# 8_RK3399_SDIO_SPI_GPIOs.net
KiCad netlist of a schematic drawn in Altium Designer
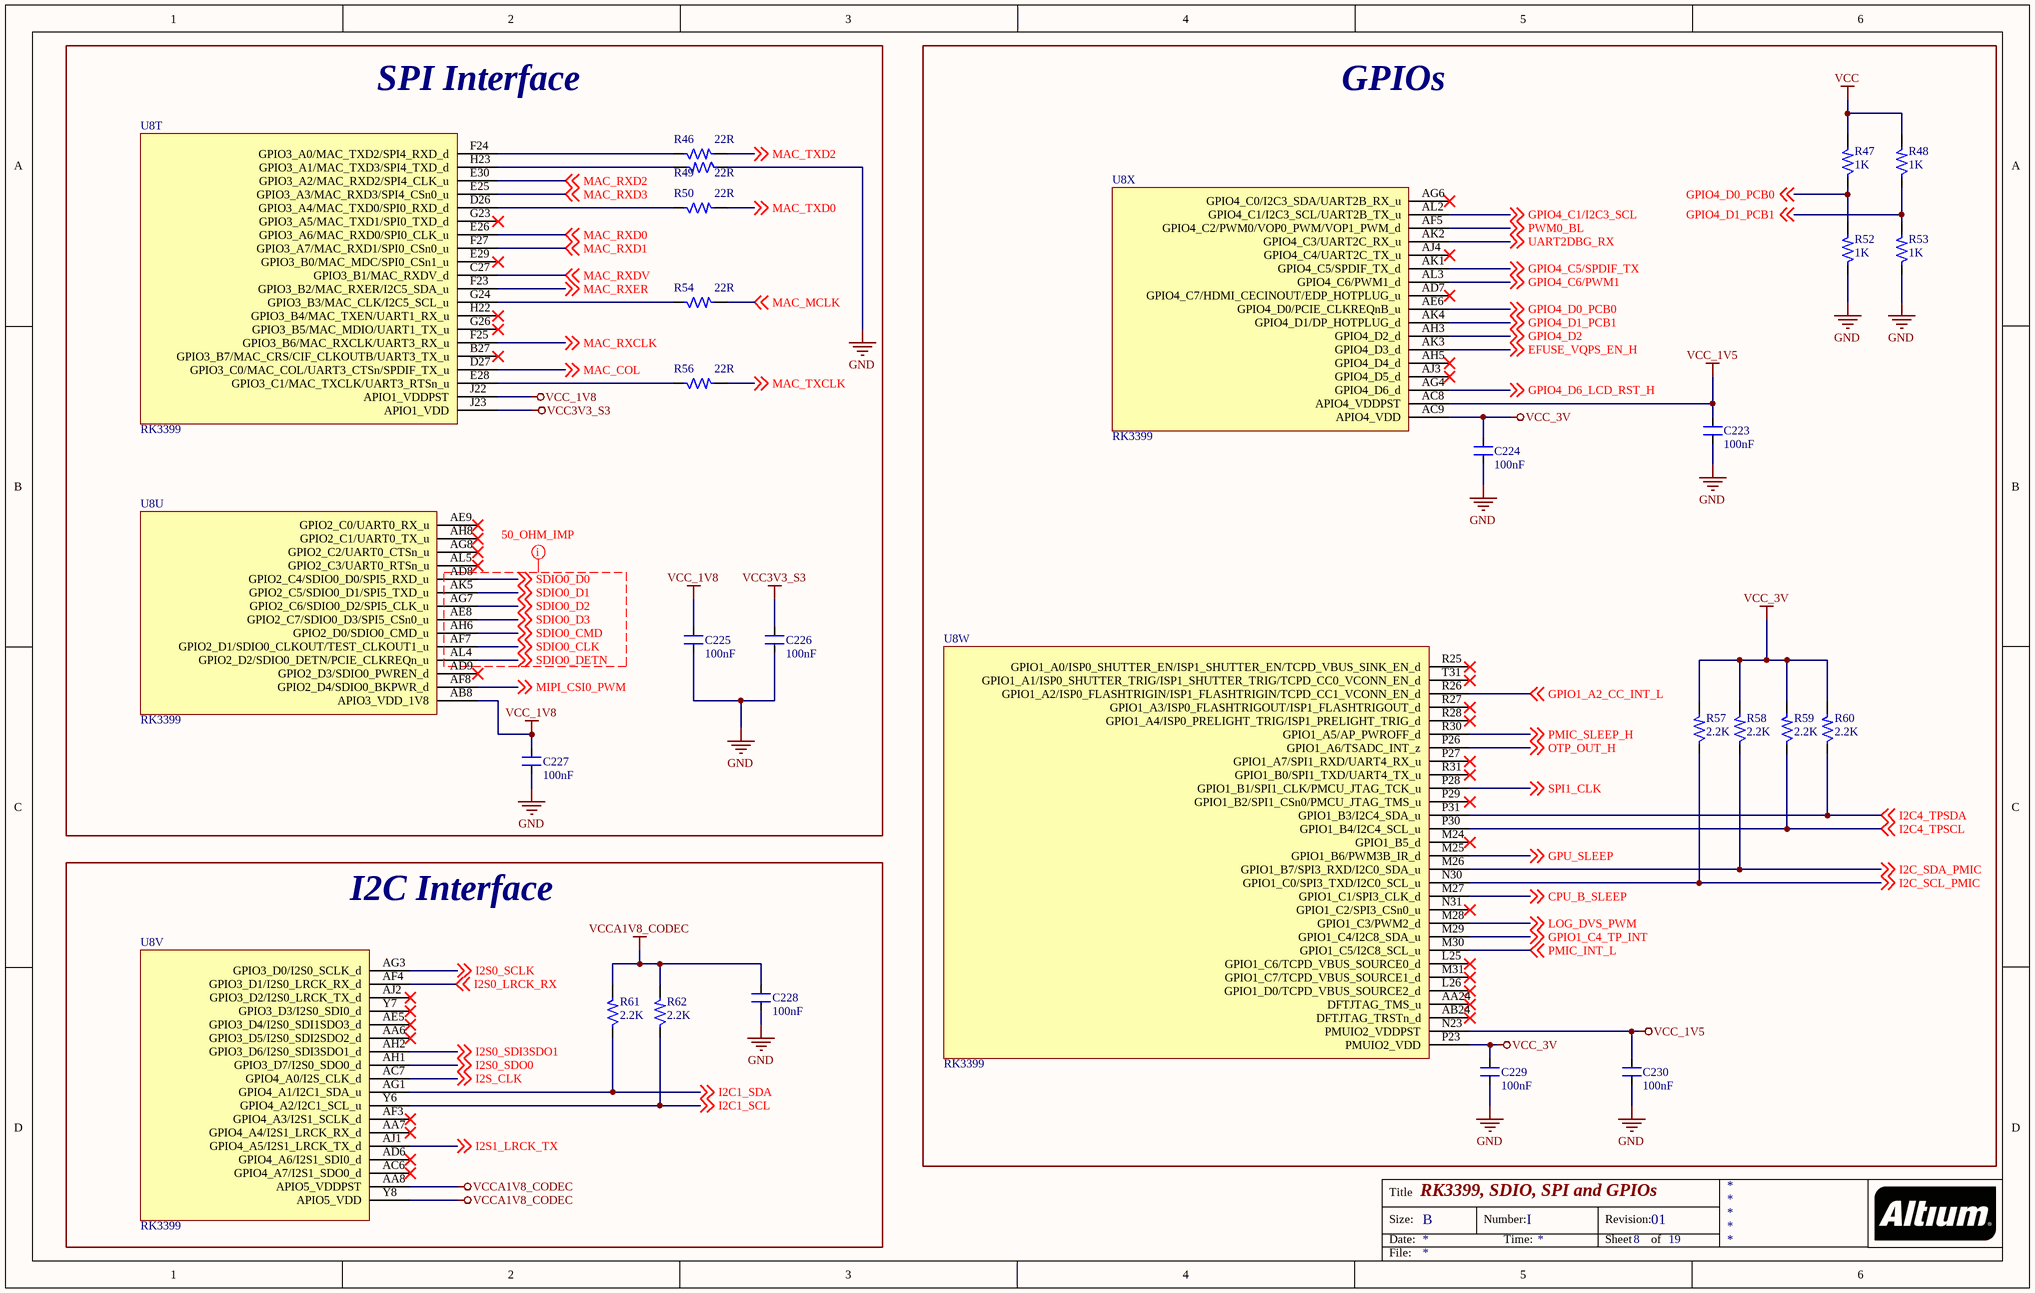
[diagram p0: [8] RK3399_SDIO_SPI_GPIOs.SchDoc]

(export (version "E")
  (design (tool "Eeschema 10.0.6"))
  (components
    (comp (ref "C223")
      (value "100nF")
      (footprint "CAP_0201")
      (description "0.1µF ±10% 25V Ceramic Capacitor X5R 0201 (0603 Metric)")
      (fields
        (field (name "MANUFACTURER") "TDK Corporation")
        (field (name "MANUFACTURER PART NUMBER") "C0603X5R1E104K030BB")
      )
      (libsource (lib "EsteemPCB_SOM_Course_intlib") (part "CAP_100nF-25V-10%-0201"))
    )
    (comp (ref "C224")
      (value "100nF")
      (footprint "CAP_0201")
      (description "0.1µF ±10% 25V Ceramic Capacitor X5R 0201 (0603 Metric)")
      (fields
        (field (name "MANUFACTURER") "TDK Corporation")
        (field (name "MANUFACTURER PART NUMBER") "C0603X5R1E104K030BB")
      )
      (libsource (lib "EsteemPCB_SOM_Course_intlib") (part "CAP_100nF-25V-10%-0201"))
    )
    (comp (ref "C225")
      (value "100nF")
      (footprint "CAP_0201")
      (description "0.1µF ±10% 25V Ceramic Capacitor X5R 0201 (0603 Metric)")
      (fields
        (field (name "MANUFACTURER") "TDK Corporation")
        (field (name "MANUFACTURER PART NUMBER") "C0603X5R1E104K030BB")
      )
      (libsource (lib "EsteemPCB_SOM_Course_intlib") (part "CAP_100nF-25V-10%-0201"))
    )
    (comp (ref "C226")
      (value "100nF")
      (footprint "CAP_0201")
      (description "0.1µF ±10% 25V Ceramic Capacitor X5R 0201 (0603 Metric)")
      (fields
        (field (name "MANUFACTURER") "TDK Corporation")
        (field (name "MANUFACTURER PART NUMBER") "C0603X5R1E104K030BB")
      )
      (libsource (lib "EsteemPCB_SOM_Course_intlib") (part "CAP_100nF-25V-10%-0201"))
    )
    (comp (ref "C227")
      (value "100nF")
      (footprint "CAP_0201")
      (description "0.1µF ±10% 25V Ceramic Capacitor X5R 0201 (0603 Metric)")
      (fields
        (field (name "MANUFACTURER") "TDK Corporation")
        (field (name "MANUFACTURER PART NUMBER") "C0603X5R1E104K030BB")
      )
      (libsource (lib "EsteemPCB_SOM_Course_intlib") (part "CAP_100nF-25V-10%-0201"))
    )
    (comp (ref "C228")
      (value "100nF")
      (footprint "CAP_0201")
      (description "0.1µF ±10% 25V Ceramic Capacitor X5R 0201 (0603 Metric)")
      (fields
        (field (name "MANUFACTURER") "TDK Corporation")
        (field (name "MANUFACTURER PART NUMBER") "C0603X5R1E104K030BB")
      )
      (libsource (lib "EsteemPCB_SOM_Course_intlib") (part "CAP_100nF-25V-10%-0201"))
    )
    (comp (ref "C229")
      (value "100nF")
      (footprint "CAP_0201")
      (description "0.1µF ±10% 25V Ceramic Capacitor X5R 0201 (0603 Metric)")
      (fields
        (field (name "MANUFACTURER") "TDK Corporation")
        (field (name "MANUFACTURER PART NUMBER") "C0603X5R1E104K030BB")
      )
      (libsource (lib "EsteemPCB_SOM_Course_intlib") (part "CAP_100nF-25V-10%-0201"))
    )
    (comp (ref "C230")
      (value "100nF")
      (footprint "CAP_0201")
      (description "0.1µF ±10% 25V Ceramic Capacitor X5R 0201 (0603 Metric)")
      (fields
        (field (name "MANUFACTURER") "TDK Corporation")
        (field (name "MANUFACTURER PART NUMBER") "C0603X5R1E104K030BB")
      )
      (libsource (lib "EsteemPCB_SOM_Course_intlib") (part "CAP_100nF-25V-10%-0201"))
    )
    (comp (ref "R46")
      (value "22R")
      (footprint "RES_0201")
      (description "22 Ohms ±1% 0.05W, 1/20W Chip Resistor 0201 (0603 Metric) Moisture Resistant Thick Film")
      (fields
        (field (name "MANUFACTURER") "Yageo")
        (field (name "MANUFACTURER PART NUMBER") "RC0201FR-0722RL")
      )
      (libsource (lib "EsteemPCB_SOM_Course_intlib") (part "RES_22R-0.05W-1%-0201"))
    )
    (comp (ref "R47")
      (value "1K")
      (footprint "RES_0201")
      (description "1 kOhms ±1% 0.05W, 1/20W Chip Resistor 0201 (0603 Metric) Thick Film")
      (fields
        (field (name "MANUFACTURER") "Yageo")
        (field (name "MANUFACTURER PART NUMBER") "RC0201FR-071KL")
      )
      (libsource (lib "EsteemPCB_SOM_Course_intlib") (part "RES_1K-0.05W-1%-0201"))
    )
    (comp (ref "R48")
      (value "1K")
      (footprint "RES_0201")
      (description "1 kOhms ±1% 0.05W, 1/20W Chip Resistor 0201 (0603 Metric) Thick Film")
      (fields
        (field (name "MANUFACTURER") "Yageo")
        (field (name "MANUFACTURER PART NUMBER") "RC0201FR-071KL")
      )
      (libsource (lib "EsteemPCB_SOM_Course_intlib") (part "RES_1K-0.05W-1%-0201"))
    )
    (comp (ref "R49")
      (value "22R")
      (footprint "RES_0201")
      (description "22 Ohms ±1% 0.05W, 1/20W Chip Resistor 0201 (0603 Metric) Moisture Resistant Thick Film")
      (fields
        (field (name "MANUFACTURER") "Yageo")
        (field (name "MANUFACTURER PART NUMBER") "RC0201FR-0722RL")
      )
      (libsource (lib "EsteemPCB_SOM_Course_intlib") (part "RES_22R-0.05W-1%-0201"))
    )
    (comp (ref "R50")
      (value "22R")
      (footprint "RES_0201")
      (description "22 Ohms ±1% 0.05W, 1/20W Chip Resistor 0201 (0603 Metric) Moisture Resistant Thick Film")
      (fields
        (field (name "MANUFACTURER") "Yageo")
        (field (name "MANUFACTURER PART NUMBER") "RC0201FR-0722RL")
      )
      (libsource (lib "EsteemPCB_SOM_Course_intlib") (part "RES_22R-0.05W-1%-0201"))
    )
    (comp (ref "R52")
      (value "1K")
      (footprint "RES_0402")
      (description "1 kOhms ±1% 0.1W, 1/10W Chip Resistor 0402 (1005 Metric) Anti-Sulfur Thin Film")
      (fields
        (field (name "MANUFACTURER") "Vishay Beyschlag/Draloric/BC Components")
        (field (name "MANUFACTURER PART NUMBER") "MCS04020C1001FE000")
      )
      (libsource (lib "EsteemPCB_SOM_Course_intlib") (part "RES_1K-0.1W-1%-0402"))
    )
    (comp (ref "R53")
      (value "1K")
      (footprint "RES_0402")
      (description "1 kOhms ±1% 0.1W, 1/10W Chip Resistor 0402 (1005 Metric) Anti-Sulfur Thin Film")
      (fields
        (field (name "MANUFACTURER") "Vishay Beyschlag/Draloric/BC Components")
        (field (name "MANUFACTURER PART NUMBER") "MCS04020C1001FE000")
      )
      (libsource (lib "EsteemPCB_SOM_Course_intlib") (part "RES_1K-0.1W-1%-0402"))
    )
    (comp (ref "R54")
      (value "22R")
      (footprint "RES_0201")
      (description "22 Ohms ±1% 0.05W, 1/20W Chip Resistor 0201 (0603 Metric) Moisture Resistant Thick Film")
      (fields
        (field (name "MANUFACTURER") "Yageo")
        (field (name "MANUFACTURER PART NUMBER") "RC0201FR-0722RL")
      )
      (libsource (lib "EsteemPCB_SOM_Course_intlib") (part "RES_22R-0.05W-1%-0201"))
    )
    (comp (ref "R56")
      (value "22R")
      (footprint "RES_0201")
      (description "22 Ohms ±1% 0.05W, 1/20W Chip Resistor 0201 (0603 Metric) Moisture Resistant Thick Film")
      (fields
        (field (name "MANUFACTURER") "Yageo")
        (field (name "MANUFACTURER PART NUMBER") "RC0201FR-0722RL")
      )
      (libsource (lib "EsteemPCB_SOM_Course_intlib") (part "RES_22R-0.05W-1%-0201"))
    )
    (comp (ref "R57")
      (value "2.2K")
      (footprint "RES_0201")
      (description "2.2 kOhms ±1% 0.05W, 1/20W Chip Resistor 0201 (0603 Metric) Thick Film")
      (fields
        (field (name "MANUFACTURER") "Stackpole Electronics Inc")
        (field (name "MANUFACTURER PART NUMBER") "RMCF0201FT2K20")
      )
      (libsource (lib "EsteemPCB_SOM_Course_intlib") (part "RES_2.2K-0.05W-1%-0201"))
    )
    (comp (ref "R58")
      (value "2.2K")
      (footprint "RES_0201")
      (description "2.2 kOhms ±1% 0.05W, 1/20W Chip Resistor 0201 (0603 Metric) Thick Film")
      (fields
        (field (name "MANUFACTURER") "Stackpole Electronics Inc")
        (field (name "MANUFACTURER PART NUMBER") "RMCF0201FT2K20")
      )
      (libsource (lib "EsteemPCB_SOM_Course_intlib") (part "RES_2.2K-0.05W-1%-0201"))
    )
    (comp (ref "R59")
      (value "2.2K")
      (footprint "RES_0201")
      (description "2.2 kOhms ±1% 0.05W, 1/20W Chip Resistor 0201 (0603 Metric) Thick Film")
      (fields
        (field (name "MANUFACTURER") "Stackpole Electronics Inc")
        (field (name "MANUFACTURER PART NUMBER") "RMCF0201FT2K20")
      )
      (libsource (lib "EsteemPCB_SOM_Course_intlib") (part "RES_2.2K-0.05W-1%-0201"))
    )
    (comp (ref "R60")
      (value "2.2K")
      (footprint "RES_0201")
      (description "2.2 kOhms ±1% 0.05W, 1/20W Chip Resistor 0201 (0603 Metric) Thick Film")
      (fields
        (field (name "MANUFACTURER") "Stackpole Electronics Inc")
        (field (name "MANUFACTURER PART NUMBER") "RMCF0201FT2K20")
      )
      (libsource (lib "EsteemPCB_SOM_Course_intlib") (part "RES_2.2K-0.05W-1%-0201"))
    )
    (comp (ref "R61")
      (value "2.2K")
      (footprint "RES_0201")
      (description "2.2 kOhms ±1% 0.05W, 1/20W Chip Resistor 0201 (0603 Metric) Thick Film")
      (fields
        (field (name "MANUFACTURER") "Stackpole Electronics Inc")
        (field (name "MANUFACTURER PART NUMBER") "RMCF0201FT2K20")
      )
      (libsource (lib "EsteemPCB_SOM_Course_intlib") (part "RES_2.2K-0.05W-1%-0201"))
    )
    (comp (ref "R62")
      (value "2.2K")
      (footprint "RES_0201")
      (description "2.2 kOhms ±1% 0.05W, 1/20W Chip Resistor 0201 (0603 Metric) Thick Film")
      (fields
        (field (name "MANUFACTURER") "Stackpole Electronics Inc")
        (field (name "MANUFACTURER PART NUMBER") "RMCF0201FT2K20")
      )
      (libsource (lib "EsteemPCB_SOM_Course_intlib") (part "RES_2.2K-0.05W-1%-0201"))
    )
    (comp (ref "U8")
      (value "RK3399")
      (footprint "FBGA828_23_826X826")
      (description "RK3399 is a low power, high performance processor for computing, personal mobile.")
      (fields (field (name "MANUFACTURER") "Rockchip"))
      (libsource (lib "EsteemPCB_SOM_Course_intlib") (part "IC_RK3399-FCBGA828"))
    )
  )
  (nets
    (net (code "1") (name "CPU_B_SLEEP") (class "Default")
      (node (ref "U8") (pin "M27") (pinfunction "GPIO1_C1/SPI3_CLK_d_M27") (pintype "passive"))
    )
    (net (code "2") (name "EFUSE_VQPS_EN_H") (class "Default")
      (node (ref "U8") (pin "AK3") (pinfunction "GPIO4_D3_d_AK3") (pintype "passive"))
    )
    (net (code "3") (name "GND") (class "Default")
      (node (ref "C223") (pin "1") (pinfunction "1_1") (pintype "passive"))
      (node (ref "C224") (pin "1") (pinfunction "1_1") (pintype "passive"))
      (node (ref "C225") (pin "1") (pinfunction "1_1") (pintype "passive"))
      (node (ref "C226") (pin "1") (pinfunction "1_1") (pintype "passive"))
      (node (ref "C227") (pin "1") (pinfunction "1_1") (pintype "passive"))
      (node (ref "C228") (pin "1") (pinfunction "1_1") (pintype "passive"))
      (node (ref "C229") (pin "1") (pinfunction "1_1") (pintype "passive"))
      (node (ref "C230") (pin "1") (pinfunction "1_1") (pintype "passive"))
      (node (ref "R49") (pin "1") (pinfunction "1_1") (pintype "passive"))
      (node (ref "R52") (pin "1") (pinfunction "1_1") (pintype "passive"))
      (node (ref "R53") (pin "1") (pinfunction "1_1") (pintype "passive"))
    )
    (net (code "4") (name "GPIO1_A2_CC_INT_L") (class "Default")
      (node (ref "U8") (pin "R26") (pinfunction "GPIO1_A2/ISP0_FLASHTRIGIN/ISP1_FLASHTRIGIN/TCPD_CC1_VCONN_EN_d_R26") (pintype "passive"))
    )
    (net (code "5") (name "GPIO1_C4_TP_INT") (class "Default")
      (node (ref "U8") (pin "M29") (pinfunction "GPIO1_C4/I2C8_SDA_u_M29") (pintype "passive"))
    )
    (net (code "6") (name "GPIO4_C1{slash}I2C3_SCL") (class "Default")
      (node (ref "U8") (pin "AL2") (pinfunction "GPIO4_C1/I2C3_SCL/UART2B_TX_u_AL2") (pintype "passive"))
    )
    (net (code "7") (name "GPIO4_C5{slash}SPDIF_TX") (class "Default")
      (node (ref "U8") (pin "AK1") (pinfunction "GPIO4_C5/SPDIF_TX_d_AK1") (pintype "passive"))
    )
    (net (code "8") (name "GPIO4_C6{slash}PWM1") (class "Default")
      (node (ref "U8") (pin "AL3") (pinfunction "GPIO4_C6/PWM1_d_AL3") (pintype "passive"))
    )
    (net (code "9") (name "GPIO4_D0_PCB0") (class "Default")
      (node (ref "R47") (pin "1") (pinfunction "1_1") (pintype "passive"))
      (node (ref "R52") (pin "2") (pinfunction "2_2") (pintype "passive"))
      (node (ref "U8") (pin "AE6") (pinfunction "GPIO4_D0/PCIE_CLKREQnB_u_AE6") (pintype "passive"))
    )
    (net (code "10") (name "GPIO4_D1_PCB1") (class "Default")
      (node (ref "R48") (pin "1") (pinfunction "1_1") (pintype "passive"))
      (node (ref "R53") (pin "2") (pinfunction "2_2") (pintype "passive"))
      (node (ref "U8") (pin "AK4") (pinfunction "GPIO4_D1/DP_HOTPLUG_d_AK4") (pintype "passive"))
    )
    (net (code "11") (name "GPIO4_D2") (class "Default")
      (node (ref "U8") (pin "AH3") (pinfunction "GPIO4_D2_d_AH3") (pintype "passive"))
    )
    (net (code "12") (name "GPIO4_D6_LCD_RST_H") (class "Default")
      (node (ref "U8") (pin "AG4") (pinfunction "GPIO4_D6_d_AG4") (pintype "passive"))
    )
    (net (code "13") (name "GPU_SLEEP") (class "Default")
      (node (ref "U8") (pin "M25") (pinfunction "GPIO1_B6/PWM3B_IR_d_M25") (pintype "passive"))
    )
    (net (code "14") (name "I2C1_SCL") (class "Default")
      (node (ref "R62") (pin "1") (pinfunction "1_1") (pintype "passive"))
      (node (ref "U8") (pin "Y6") (pinfunction "GPIO4_A2/I2C1_SCL_u_Y6") (pintype "passive"))
    )
    (net (code "15") (name "I2C1_SDA") (class "Default")
      (node (ref "R61") (pin "1") (pinfunction "1_1") (pintype "passive"))
      (node (ref "U8") (pin "AG1") (pinfunction "GPIO4_A1/I2C1_SDA_u_AG1") (pintype "passive"))
    )
    (net (code "16") (name "I2C4_TPSCL") (class "Default")
      (node (ref "R59") (pin "1") (pinfunction "1_1") (pintype "passive"))
      (node (ref "U8") (pin "P30") (pinfunction "GPIO1_B4/I2C4_SCL_u_P30") (pintype "passive"))
    )
    (net (code "17") (name "I2C4_TPSDA") (class "Default")
      (node (ref "R60") (pin "1") (pinfunction "1_1") (pintype "passive"))
      (node (ref "U8") (pin "P31") (pinfunction "GPIO1_B3/I2C4_SDA_u_P31") (pintype "passive"))
    )
    (net (code "18") (name "I2C_SCL_PMIC") (class "Default")
      (node (ref "R57") (pin "1") (pinfunction "1_1") (pintype "passive"))
      (node (ref "U8") (pin "N30") (pinfunction "GPIO1_C0/SPI3_TXD/I2C0_SCL_u_N30") (pintype "passive"))
    )
    (net (code "19") (name "I2C_SDA_PMIC") (class "Default")
      (node (ref "R58") (pin "1") (pinfunction "1_1") (pintype "passive"))
      (node (ref "U8") (pin "M26") (pinfunction "GPIO1_B7/SPI3_RXD/I2C0_SDA_u_M26") (pintype "passive"))
    )
    (net (code "20") (name "I2S0_LRCK_RX") (class "Default")
      (node (ref "U8") (pin "AF4") (pinfunction "GPIO3_D1/I2S0_LRCK_RX_d_AF4") (pintype "passive"))
    )
    (net (code "21") (name "I2S0_SCLK") (class "Default")
      (node (ref "U8") (pin "AG3") (pinfunction "GPIO3_D0/I2S0_SCLK_d_AG3") (pintype "passive"))
    )
    (net (code "22") (name "I2S0_SDI3SDO1") (class "Default")
      (node (ref "U8") (pin "AH2") (pinfunction "GPIO3_D6/I2S0_SDI3SDO1_d_AH2") (pintype "passive"))
    )
    (net (code "23") (name "I2S0_SDO0") (class "Default")
      (node (ref "U8") (pin "AH1") (pinfunction "GPIO3_D7/I2S0_SDO0_d_AH1") (pintype "passive"))
    )
    (net (code "24") (name "I2S1_LRCK_TX") (class "Default")
      (node (ref "U8") (pin "AJ1") (pinfunction "GPIO4_A5/I2S1_LRCK_TX_d_AJ1") (pintype "passive"))
    )
    (net (code "25") (name "I2S_CLK") (class "Default")
      (node (ref "U8") (pin "AC7") (pinfunction "GPIO4_A0/I2S_CLK_d_AC7") (pintype "passive"))
    )
    (net (code "26") (name "LOG_DVS_PWM") (class "Default")
      (node (ref "U8") (pin "M28") (pinfunction "GPIO1_C3/PWM2_d_M28") (pintype "passive"))
    )
    (net (code "27") (name "MAC_COL") (class "Default")
      (node (ref "U8") (pin "D27") (pinfunction "GPIO3_C0/MAC_COL/UART3_CTSn/SPDIF_TX_u_D27") (pintype "passive"))
    )
    (net (code "28") (name "MAC_MCLK") (class "Default")
      (node (ref "R54") (pin "2") (pinfunction "2_2") (pintype "passive"))
    )
    (net (code "29") (name "MAC_RXCLK") (class "Default")
      (node (ref "U8") (pin "F25") (pinfunction "GPIO3_B6/MAC_RXCLK/UART3_RX_u_F25") (pintype "passive"))
    )
    (net (code "30") (name "MAC_RXD0") (class "Default")
      (node (ref "U8") (pin "E26") (pinfunction "GPIO3_A6/MAC_RXD0/SPI0_CLK_u_E26") (pintype "passive"))
    )
    (net (code "31") (name "MAC_RXD1") (class "Default")
      (node (ref "U8") (pin "F27") (pinfunction "GPIO3_A7/MAC_RXD1/SPI0_CSn0_u_F27") (pintype "passive"))
    )
    (net (code "32") (name "MAC_RXD2") (class "Default")
      (node (ref "U8") (pin "E30") (pinfunction "GPIO3_A2/MAC_RXD2/SPI4_CLK_u_E30") (pintype "passive"))
    )
    (net (code "33") (name "MAC_RXD3") (class "Default")
      (node (ref "U8") (pin "E25") (pinfunction "GPIO3_A3/MAC_RXD3/SPI4_CSn0_u_E25") (pintype "passive"))
    )
    (net (code "34") (name "MAC_RXDV") (class "Default")
      (node (ref "U8") (pin "C27") (pinfunction "GPIO3_B1/MAC_RXDV_d_C27") (pintype "passive"))
    )
    (net (code "35") (name "MAC_RXER") (class "Default")
      (node (ref "U8") (pin "F23") (pinfunction "GPIO3_B2/MAC_RXER/I2C5_SDA_u_F23") (pintype "passive"))
    )
    (net (code "36") (name "MAC_TXCLK") (class "Default")
      (node (ref "R56") (pin "2") (pinfunction "2_2") (pintype "passive"))
    )
    (net (code "37") (name "MAC_TXD0") (class "Default")
      (node (ref "R50") (pin "2") (pinfunction "2_2") (pintype "passive"))
    )
    (net (code "38") (name "MAC_TXD2") (class "Default")
      (node (ref "R46") (pin "2") (pinfunction "2_2") (pintype "passive"))
    )
    (net (code "39") (name "MIPI_CSI0_PWM") (class "Default")
      (node (ref "U8") (pin "AF8") (pinfunction "GPIO2_D4/SDIO0_BKPWR_d_AF8") (pintype "passive"))
    )
    (net (code "40") (name "Net-(U8T-GPIO3_A0{slash}MAC_TXD2{slash}SPI4_RXD_d)") (class "Default")
      (node (ref "R46") (pin "1") (pinfunction "1_1") (pintype "passive"))
      (node (ref "U8") (pin "F24") (pinfunction "GPIO3_A0/MAC_TXD2/SPI4_RXD_d_F24") (pintype "passive"))
    )
    (net (code "41") (name "Net-(U8T-GPIO3_A1{slash}MAC_TXD3{slash}SPI4_TXD_d)") (class "Default")
      (node (ref "R49") (pin "2") (pinfunction "2_2") (pintype "passive"))
      (node (ref "U8") (pin "H23") (pinfunction "GPIO3_A1/MAC_TXD3/SPI4_TXD_d_H23") (pintype "passive"))
    )
    (net (code "42") (name "Net-(U8T-GPIO3_A4{slash}MAC_TXD0{slash}SPI0_RXD_d)") (class "Default")
      (node (ref "R50") (pin "1") (pinfunction "1_1") (pintype "passive"))
      (node (ref "U8") (pin "D26") (pinfunction "GPIO3_A4/MAC_TXD0/SPI0_RXD_d_D26") (pintype "passive"))
    )
    (net (code "43") (name "Net-(U8T-GPIO3_B3{slash}MAC_CLK{slash}I2C5_SCL_u)") (class "Default")
      (node (ref "R54") (pin "1") (pinfunction "1_1") (pintype "passive"))
      (node (ref "U8") (pin "G24") (pinfunction "GPIO3_B3/MAC_CLK/I2C5_SCL_u_G24") (pintype "passive"))
    )
    (net (code "44") (name "Net-(U8T-GPIO3_C1{slash}MAC_TXCLK{slash}UART3_RTSn_u)") (class "Default")
      (node (ref "R56") (pin "1") (pinfunction "1_1") (pintype "passive"))
      (node (ref "U8") (pin "E28") (pinfunction "GPIO3_C1/MAC_TXCLK/UART3_RTSn_u_E28") (pintype "passive"))
    )
    (net (code "45") (name "OTP_OUT_H") (class "Default")
      (node (ref "U8") (pin "P26") (pinfunction "GPIO1_A6/TSADC_INT_z_P26") (pintype "passive"))
    )
    (net (code "46") (name "PMIC_INT_L") (class "Default")
      (node (ref "U8") (pin "M30") (pinfunction "GPIO1_C5/I2C8_SCL_u_M30") (pintype "passive"))
    )
    (net (code "47") (name "PMIC_SLEEP_H") (class "Default")
      (node (ref "U8") (pin "R30") (pinfunction "GPIO1_A5/AP_PWROFF_d_R30") (pintype "passive"))
    )
    (net (code "48") (name "PWM0_BL") (class "Default")
      (node (ref "U8") (pin "AF5") (pinfunction "GPIO4_C2/PWM0/VOP0_PWM/VOP1_PWM_d_AF5") (pintype "passive"))
    )
    (net (code "49") (name "SDIO0_CLK") (class "Default")
      (node (ref "U8") (pin "AF7") (pinfunction "GPIO2_D1/SDIO0_CLKOUT/TEST_CLKOUT1_u_AF7") (pintype "passive"))
    )
    (net (code "50") (name "SDIO0_CMD") (class "Default")
      (node (ref "U8") (pin "AH6") (pinfunction "GPIO2_D0/SDIO0_CMD_u_AH6") (pintype "passive"))
    )
    (net (code "51") (name "SDIO0_D0") (class "Default")
      (node (ref "U8") (pin "AD8") (pinfunction "GPIO2_C4/SDIO0_D0/SPI5_RXD_u_AD8") (pintype "passive"))
    )
    (net (code "52") (name "SDIO0_D1") (class "Default")
      (node (ref "U8") (pin "AK5") (pinfunction "GPIO2_C5/SDIO0_D1/SPI5_TXD_u_AK5") (pintype "passive"))
    )
    (net (code "53") (name "SDIO0_D2") (class "Default")
      (node (ref "U8") (pin "AG7") (pinfunction "GPIO2_C6/SDIO0_D2/SPI5_CLK_u_AG7") (pintype "passive"))
    )
    (net (code "54") (name "SDIO0_D3") (class "Default")
      (node (ref "U8") (pin "AE8") (pinfunction "GPIO2_C7/SDIO0_D3/SPI5_CSn0_u_AE8") (pintype "passive"))
    )
    (net (code "55") (name "SDIO0_DETN") (class "Default")
      (node (ref "U8") (pin "AL4") (pinfunction "GPIO2_D2/SDIO0_DETN/PCIE_CLKREQn_u_AL4") (pintype "passive"))
    )
    (net (code "56") (name "SPI1_CLK") (class "Default")
      (node (ref "U8") (pin "P28") (pinfunction "GPIO1_B1/SPI1_CLK/PMCU_JTAG_TCK_u_P28") (pintype "passive"))
    )
    (net (code "57") (name "UART2DBG_RX") (class "Default")
      (node (ref "U8") (pin "AK2") (pinfunction "GPIO4_C3/UART2C_RX_u_AK2") (pintype "passive"))
    )
    (net (code "58") (name "VCC") (class "Default")
      (node (ref "R47") (pin "2") (pinfunction "2_2") (pintype "passive"))
      (node (ref "R48") (pin "2") (pinfunction "2_2") (pintype "passive"))
    )
    (net (code "59") (name "VCC3V3_S3") (class "Default")
      (node (ref "C226") (pin "2") (pinfunction "2_2") (pintype "passive"))
      (node (ref "U8") (pin "J23") (pinfunction "APIO1_VDD_J23") (pintype "passive"))
    )
    (net (code "60") (name "VCCA1V8_CODEC") (class "Default")
      (node (ref "C228") (pin "2") (pinfunction "2_2") (pintype "passive"))
      (node (ref "R61") (pin "2") (pinfunction "2_2") (pintype "passive"))
      (node (ref "R62") (pin "2") (pinfunction "2_2") (pintype "passive"))
      (node (ref "U8") (pin "AA8") (pinfunction "APIO5_VDDPST_AA8") (pintype "passive"))
      (node (ref "U8") (pin "Y8") (pinfunction "APIO5_VDD_Y8") (pintype "passive"))
    )
    (net (code "61") (name "VCC_1V5") (class "Default")
      (node (ref "C223") (pin "2") (pinfunction "2_2") (pintype "passive"))
      (node (ref "C230") (pin "2") (pinfunction "2_2") (pintype "passive"))
      (node (ref "U8") (pin "AC8") (pinfunction "APIO4_VDDPST_AC8") (pintype "passive"))
      (node (ref "U8") (pin "N23") (pinfunction "PMUIO2_VDDPST_N23") (pintype "passive"))
    )
    (net (code "62") (name "VCC_1V8") (class "Default")
      (node (ref "C225") (pin "2") (pinfunction "2_2") (pintype "passive"))
      (node (ref "C227") (pin "2") (pinfunction "2_2") (pintype "passive"))
      (node (ref "U8") (pin "AB8") (pinfunction "APIO3_VDD_1V8_AB8") (pintype "passive"))
      (node (ref "U8") (pin "J22") (pinfunction "APIO1_VDDPST_J22") (pintype "passive"))
    )
    (net (code "63") (name "VCC_3V") (class "Default")
      (node (ref "C224") (pin "2") (pinfunction "2_2") (pintype "passive"))
      (node (ref "C229") (pin "2") (pinfunction "2_2") (pintype "passive"))
      (node (ref "R57") (pin "2") (pinfunction "2_2") (pintype "passive"))
      (node (ref "R58") (pin "2") (pinfunction "2_2") (pintype "passive"))
      (node (ref "R59") (pin "2") (pinfunction "2_2") (pintype "passive"))
      (node (ref "R60") (pin "2") (pinfunction "2_2") (pintype "passive"))
      (node (ref "U8") (pin "AC9") (pinfunction "APIO4_VDD_AC9") (pintype "passive"))
      (node (ref "U8") (pin "P23") (pinfunction "PMUIO2_VDD_P23") (pintype "passive"))
    )
    (net (code "64") (name "unconnected-(U8T-GPIO3_A5{slash}MAC_TXD1{slash}SPI0_TXD_d-PadG23)") (class "Default")
      (node (ref "U8") (pin "G23") (pinfunction "GPIO3_A5/MAC_TXD1/SPI0_TXD_d_G23") (pintype "passive+no_connect"))
    )
    (net (code "65") (name "unconnected-(U8T-GPIO3_B0{slash}MAC_MDC{slash}SPI0_CSn1_u-PadE29)") (class "Default")
      (node (ref "U8") (pin "E29") (pinfunction "GPIO3_B0/MAC_MDC/SPI0_CSn1_u_E29") (pintype "passive+no_connect"))
    )
    (net (code "66") (name "unconnected-(U8T-GPIO3_B4{slash}MAC_TXEN{slash}UART1_RX_u-PadH22)") (class "Default")
      (node (ref "U8") (pin "H22") (pinfunction "GPIO3_B4/MAC_TXEN/UART1_RX_u_H22") (pintype "passive+no_connect"))
    )
    (net (code "67") (name "unconnected-(U8T-GPIO3_B5{slash}MAC_MDIO{slash}UART1_TX_u-PadG26)") (class "Default")
      (node (ref "U8") (pin "G26") (pinfunction "GPIO3_B5/MAC_MDIO/UART1_TX_u_G26") (pintype "passive+no_connect"))
    )
    (net (code "68") (name "unconnected-(U8T-GPIO3_B7{slash}MAC_CRS{slash}CIF_CLKOUTB{slash}UART3_TX_u-PadB27)") (class "Default")
      (node (ref "U8") (pin "B27") (pinfunction "GPIO3_B7/MAC_CRS/CIF_CLKOUTB/UART3_TX_u_B27") (pintype "passive+no_connect"))
    )
    (net (code "69") (name "unconnected-(U8U-GPIO2_C0{slash}UART0_RX_u-PadAE9)") (class "Default")
      (node (ref "U8") (pin "AE9") (pinfunction "GPIO2_C0/UART0_RX_u_AE9") (pintype "passive+no_connect"))
    )
    (net (code "70") (name "unconnected-(U8U-GPIO2_C1{slash}UART0_TX_u-PadAH8)") (class "Default")
      (node (ref "U8") (pin "AH8") (pinfunction "GPIO2_C1/UART0_TX_u_AH8") (pintype "passive+no_connect"))
    )
    (net (code "71") (name "unconnected-(U8U-GPIO2_C2{slash}UART0_CTSn_u-PadAG8)") (class "Default")
      (node (ref "U8") (pin "AG8") (pinfunction "GPIO2_C2/UART0_CTSn_u_AG8") (pintype "passive+no_connect"))
    )
    (net (code "72") (name "unconnected-(U8U-GPIO2_C3{slash}UART0_RTSn_u-PadAL5)") (class "Default")
      (node (ref "U8") (pin "AL5") (pinfunction "GPIO2_C3/UART0_RTSn_u_AL5") (pintype "passive+no_connect"))
    )
    (net (code "73") (name "unconnected-(U8U-GPIO2_D3{slash}SDIO0_PWREN_d-PadAD9)") (class "Default")
      (node (ref "U8") (pin "AD9") (pinfunction "GPIO2_D3/SDIO0_PWREN_d_AD9") (pintype "passive+no_connect"))
    )
    (net (code "74") (name "unconnected-(U8V-GPIO3_D2{slash}I2S0_LRCK_TX_d-PadAJ2)") (class "Default")
      (node (ref "U8") (pin "AJ2") (pinfunction "GPIO3_D2/I2S0_LRCK_TX_d_AJ2") (pintype "passive+no_connect"))
    )
    (net (code "75") (name "unconnected-(U8V-GPIO3_D3{slash}I2S0_SDI0_d-PadY7)") (class "Default")
      (node (ref "U8") (pin "Y7") (pinfunction "GPIO3_D3/I2S0_SDI0_d_Y7") (pintype "passive+no_connect"))
    )
    (net (code "76") (name "unconnected-(U8V-GPIO3_D4{slash}I2S0_SDI1SDO3_d-PadAE5)") (class "Default")
      (node (ref "U8") (pin "AE5") (pinfunction "GPIO3_D4/I2S0_SDI1SDO3_d_AE5") (pintype "passive+no_connect"))
    )
    (net (code "77") (name "unconnected-(U8V-GPIO3_D5{slash}I2S0_SDI2SDO2_d-PadAA6)") (class "Default")
      (node (ref "U8") (pin "AA6") (pinfunction "GPIO3_D5/I2S0_SDI2SDO2_d_AA6") (pintype "passive+no_connect"))
    )
    (net (code "78") (name "unconnected-(U8V-GPIO4_A3{slash}I2S1_SCLK_d-PadAF3)") (class "Default")
      (node (ref "U8") (pin "AF3") (pinfunction "GPIO4_A3/I2S1_SCLK_d_AF3") (pintype "passive+no_connect"))
    )
    (net (code "79") (name "unconnected-(U8V-GPIO4_A4{slash}I2S1_LRCK_RX_d-PadAA7)") (class "Default")
      (node (ref "U8") (pin "AA7") (pinfunction "GPIO4_A4/I2S1_LRCK_RX_d_AA7") (pintype "passive+no_connect"))
    )
    (net (code "80") (name "unconnected-(U8V-GPIO4_A6{slash}I2S1_SDI0_d-PadAD6)") (class "Default")
      (node (ref "U8") (pin "AD6") (pinfunction "GPIO4_A6/I2S1_SDI0_d_AD6") (pintype "passive+no_connect"))
    )
    (net (code "81") (name "unconnected-(U8V-GPIO4_A7{slash}I2S1_SDO0_d-PadAC6)") (class "Default")
      (node (ref "U8") (pin "AC6") (pinfunction "GPIO4_A7/I2S1_SDO0_d_AC6") (pintype "passive+no_connect"))
    )
    (net (code "82") (name "unconnected-(U8W-DFTJTAG_TMS_u-PadAA24)") (class "Default")
      (node (ref "U8") (pin "AA24") (pinfunction "DFTJTAG_TMS_u_AA24") (pintype "passive+no_connect"))
    )
    (net (code "83") (name "unconnected-(U8W-DFTJTAG_TRSTn_d-PadAB24)") (class "Default")
      (node (ref "U8") (pin "AB24") (pinfunction "DFTJTAG_TRSTn_d_AB24") (pintype "passive+no_connect"))
    )
    (net (code "84") (name "unconnected-(U8W-GPIO1_A0{slash}ISP0_SHUTTER_EN{slash}ISP1_SHUTTER_EN{slash}TCPD_VBUS_SINK_EN_d-PadR25)") (class "Default")
      (node (ref "U8") (pin "R25") (pinfunction "GPIO1_A0/ISP0_SHUTTER_EN/ISP1_SHUTTER_EN/TCPD_VBUS_SINK_EN_d_R25") (pintype "passive+no_connect"))
    )
    (net (code "85") (name "unconnected-(U8W-GPIO1_A1{slash}ISP0_SHUTTER_TRIG{slash}ISP1_SHUTTER_TRIG{slash}TCPD_CC0_VCONN_EN_d-PadT31)") (class "Default")
      (node (ref "U8") (pin "T31") (pinfunction "GPIO1_A1/ISP0_SHUTTER_TRIG/ISP1_SHUTTER_TRIG/TCPD_CC0_VCONN_EN_d_T31") (pintype "passive+no_connect"))
    )
    (net (code "86") (name "unconnected-(U8W-GPIO1_A3{slash}ISP0_FLASHTRIGOUT{slash}ISP1_FLASHTRIGOUT_d-PadR27)") (class "Default")
      (node (ref "U8") (pin "R27") (pinfunction "GPIO1_A3/ISP0_FLASHTRIGOUT/ISP1_FLASHTRIGOUT_d_R27") (pintype "passive+no_connect"))
    )
    (net (code "87") (name "unconnected-(U8W-GPIO1_A4{slash}ISP0_PRELIGHT_TRIG{slash}ISP1_PRELIGHT_TRIG_d-PadR28)") (class "Default")
      (node (ref "U8") (pin "R28") (pinfunction "GPIO1_A4/ISP0_PRELIGHT_TRIG/ISP1_PRELIGHT_TRIG_d_R28") (pintype "passive+no_connect"))
    )
    (net (code "88") (name "unconnected-(U8W-GPIO1_A7{slash}SPI1_RXD{slash}UART4_RX_u-PadP27)") (class "Default")
      (node (ref "U8") (pin "P27") (pinfunction "GPIO1_A7/SPI1_RXD/UART4_RX_u_P27") (pintype "passive+no_connect"))
    )
    (net (code "89") (name "unconnected-(U8W-GPIO1_B0{slash}SPI1_TXD{slash}UART4_TX_u-PadR31)") (class "Default")
      (node (ref "U8") (pin "R31") (pinfunction "GPIO1_B0/SPI1_TXD/UART4_TX_u_R31") (pintype "passive+no_connect"))
    )
    (net (code "90") (name "unconnected-(U8W-GPIO1_B2{slash}SPI1_CSn0{slash}PMCU_JTAG_TMS_u-PadP29)") (class "Default")
      (node (ref "U8") (pin "P29") (pinfunction "GPIO1_B2/SPI1_CSn0/PMCU_JTAG_TMS_u_P29") (pintype "passive+no_connect"))
    )
    (net (code "91") (name "unconnected-(U8W-GPIO1_B5_d-PadM24)") (class "Default")
      (node (ref "U8") (pin "M24") (pinfunction "GPIO1_B5_d_M24") (pintype "passive+no_connect"))
    )
    (net (code "92") (name "unconnected-(U8W-GPIO1_C2{slash}SPI3_CSn0_u-PadN31)") (class "Default")
      (node (ref "U8") (pin "N31") (pinfunction "GPIO1_C2/SPI3_CSn0_u_N31") (pintype "passive+no_connect"))
    )
    (net (code "93") (name "unconnected-(U8W-GPIO1_C6{slash}TCPD_VBUS_SOURCE0_d-PadL25)") (class "Default")
      (node (ref "U8") (pin "L25") (pinfunction "GPIO1_C6/TCPD_VBUS_SOURCE0_d_L25") (pintype "passive+no_connect"))
    )
    (net (code "94") (name "unconnected-(U8W-GPIO1_C7{slash}TCPD_VBUS_SOURCE1_d-PadM31)") (class "Default")
      (node (ref "U8") (pin "M31") (pinfunction "GPIO1_C7/TCPD_VBUS_SOURCE1_d_M31") (pintype "passive+no_connect"))
    )
    (net (code "95") (name "unconnected-(U8W-GPIO1_D0{slash}TCPD_VBUS_SOURCE2_d-PadL26)") (class "Default")
      (node (ref "U8") (pin "L26") (pinfunction "GPIO1_D0/TCPD_VBUS_SOURCE2_d_L26") (pintype "passive+no_connect"))
    )
    (net (code "96") (name "unconnected-(U8X-GPIO4_C0{slash}I2C3_SDA{slash}UART2B_RX_u-PadAG6)") (class "Default")
      (node (ref "U8") (pin "AG6") (pinfunction "GPIO4_C0/I2C3_SDA/UART2B_RX_u_AG6") (pintype "passive+no_connect"))
    )
    (net (code "97") (name "unconnected-(U8X-GPIO4_C4{slash}UART2C_TX_u-PadAJ4)") (class "Default")
      (node (ref "U8") (pin "AJ4") (pinfunction "GPIO4_C4/UART2C_TX_u_AJ4") (pintype "passive+no_connect"))
    )
    (net (code "98") (name "unconnected-(U8X-GPIO4_C7{slash}HDMI_CECINOUT{slash}EDP_HOTPLUG_u-PadAD7)") (class "Default")
      (node (ref "U8") (pin "AD7") (pinfunction "GPIO4_C7/HDMI_CECINOUT/EDP_HOTPLUG_u_AD7") (pintype "passive+no_connect"))
    )
    (net (code "99") (name "unconnected-(U8X-GPIO4_D4_d-PadAH5)") (class "Default")
      (node (ref "U8") (pin "AH5") (pinfunction "GPIO4_D4_d_AH5") (pintype "passive+no_connect"))
    )
    (net (code "100") (name "unconnected-(U8X-GPIO4_D5_d-PadAJ3)") (class "Default")
      (node (ref "U8") (pin "AJ3") (pinfunction "GPIO4_D5_d_AJ3") (pintype "passive+no_connect"))
    )
  )
)
